# FAAFR.net
KiCad netlist of a schematic drawn in Altium Designer
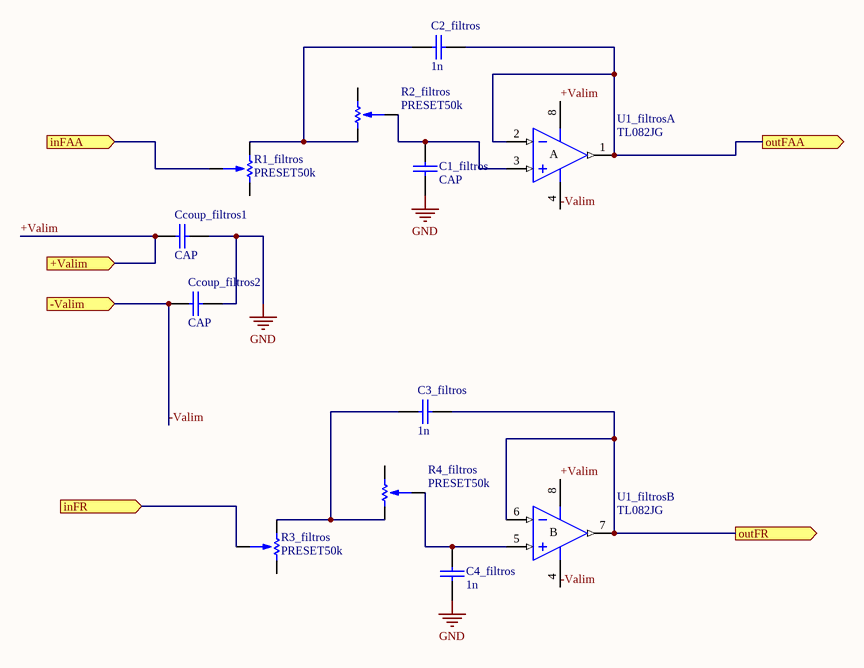
[diagram p0: FAAFR.SchDoc]

(export (version "E")
  (design (tool "Eeschema 10.0.6"))
  (components
    (comp (ref "C1_filtros") (value "CAP") (footprint "CAP200") (libsource (lib "LIBEBAL") (part "CAP")))
    (comp (ref "C2_filtros") (value "1n") (footprint "CAP200") (libsource (lib "LIBEBAL") (part "CAP")))
    (comp (ref "C3_filtros") (value "1n") (footprint "CAP200") (libsource (lib "LIBEBAL") (part "CAP")))
    (comp (ref "C4_filtros") (value "1n") (footprint "CAP200") (libsource (lib "LIBEBAL") (part "CAP")))
    (comp (ref "Ccoup_filtros1") (value "CAP") (footprint "CAP200") (libsource (lib "LIBEBAL") (part "CAP")))
    (comp (ref "Ccoup_filtros2") (value "CAP") (footprint "CAP200") (libsource (lib "LIBEBAL") (part "CAP")))
    (comp (ref "R1_filtros")
      (value "PRESET50k")
      (footprint "PRESET V")
      (libsource (lib "LIBEBAL") (part "PRESET"))
    )
    (comp (ref "R2_filtros")
      (value "PRESET50k")
      (footprint "PRESET V")
      (libsource (lib "LIBEBAL") (part "PRESET"))
    )
    (comp (ref "R3_filtros")
      (value "PRESET50k")
      (footprint "PRESET V")
      (libsource (lib "LIBEBAL") (part "PRESET"))
    )
    (comp (ref "R4_filtros")
      (value "PRESET50k")
      (footprint "PRESET V")
      (libsource (lib "LIBEBAL") (part "PRESET"))
    )
    (comp (ref "U1_filtros")
      (value "TL082JG")
      (footprint "JG008")
      (description "JFET-Input Operational Amplifier")
      (fields (field (name "PUBLISHER") "Altium Limited"))
      (libsource (lib "TI Operational Amplifier") (part "TL082JG"))
    )
  )
  (nets
    (net (code "1") (name "/+Valim") (class "Default")
      (node (ref "Ccoup_filtros1") (pin "1") (pinfunction "1_1") (pintype "passive"))
      (node (ref "U1_filtros") (pin "8") (pinfunction "V+_8") (pintype "power_in"))
    )
    (net (code "2") (name "/-Valim") (class "Default")
      (node (ref "Ccoup_filtros2") (pin "1") (pinfunction "1_1") (pintype "passive"))
      (node (ref "U1_filtros") (pin "4") (pinfunction "V-_4") (pintype "power_in"))
    )
    (net (code "3") (name "/inFAA") (class "Default")
      (node (ref "R1_filtros") (pin "2") (pinfunction "2_2") (pintype "passive"))
    )
    (net (code "4") (name "/inFR") (class "Default")
      (node (ref "R3_filtros") (pin "2") (pinfunction "2_2") (pintype "passive"))
    )
    (net (code "5") (name "/outFAA") (class "Default")
      (node (ref "C2_filtros") (pin "2") (pinfunction "2_2") (pintype "passive"))
      (node (ref "U1_filtros") (pin "1") (pinfunction "OUT_1") (pintype "output"))
      (node (ref "U1_filtros") (pin "2") (pinfunction "IN-_2") (pintype "input"))
    )
    (net (code "6") (name "/outFR") (class "Default")
      (node (ref "C3_filtros") (pin "2") (pinfunction "2_2") (pintype "passive"))
      (node (ref "U1_filtros") (pin "6") (pinfunction "IN-_6") (pintype "input"))
      (node (ref "U1_filtros") (pin "7") (pinfunction "OUT_7") (pintype "output"))
    )
    (net (code "7") (name "GND") (class "Default")
      (node (ref "C1_filtros") (pin "2") (pinfunction "2_2") (pintype "passive"))
      (node (ref "C4_filtros") (pin "1") (pinfunction "1_1") (pintype "passive"))
      (node (ref "Ccoup_filtros1") (pin "2") (pinfunction "2_2") (pintype "passive"))
      (node (ref "Ccoup_filtros2") (pin "2") (pinfunction "2_2") (pintype "passive"))
    )
    (net (code "8") (name "Net-(C2_filtros-Pad1)") (class "Default")
      (node (ref "C2_filtros") (pin "1") (pinfunction "1_1") (pintype "passive"))
      (node (ref "R1_filtros") (pin "3") (pinfunction "3_3") (pintype "passive"))
      (node (ref "R2_filtros") (pin "3") (pinfunction "3_3") (pintype "passive"))
    )
    (net (code "9") (name "Net-(C3_filtros-Pad1)") (class "Default")
      (node (ref "C3_filtros") (pin "1") (pinfunction "1_1") (pintype "passive"))
      (node (ref "R3_filtros") (pin "3") (pinfunction "3_3") (pintype "passive"))
      (node (ref "R4_filtros") (pin "3") (pinfunction "3_3") (pintype "passive"))
    )
    (net (code "10") (name "Net-(U1_filtrosA-IN+)") (class "Default")
      (node (ref "C1_filtros") (pin "1") (pinfunction "1_1") (pintype "passive"))
      (node (ref "R2_filtros") (pin "2") (pinfunction "2_2") (pintype "passive"))
      (node (ref "U1_filtros") (pin "3") (pinfunction "IN+_3") (pintype "input"))
    )
    (net (code "11") (name "Net-(U1_filtrosB-IN+)") (class "Default")
      (node (ref "C4_filtros") (pin "2") (pinfunction "2_2") (pintype "passive"))
      (node (ref "R4_filtros") (pin "2") (pinfunction "2_2") (pintype "passive"))
      (node (ref "U1_filtros") (pin "5") (pinfunction "IN+_5") (pintype "input"))
    )
    (net (code "12") (name "unconnected-(R1_filtros-Pad1)") (class "Default")
      (node (ref "R1_filtros") (pin "1") (pinfunction "1_1") (pintype "passive"))
    )
    (net (code "13") (name "unconnected-(R2_filtros-Pad1)") (class "Default")
      (node (ref "R2_filtros") (pin "1") (pinfunction "1_1") (pintype "passive"))
    )
    (net (code "14") (name "unconnected-(R3_filtros-Pad1)") (class "Default")
      (node (ref "R3_filtros") (pin "1") (pinfunction "1_1") (pintype "passive"))
    )
    (net (code "15") (name "unconnected-(R4_filtros-Pad1)") (class "Default")
      (node (ref "R4_filtros") (pin "1") (pinfunction "1_1") (pintype "passive"))
    )
  )
)
